# Power.net
KiCad netlist of a schematic drawn in Altium Designer
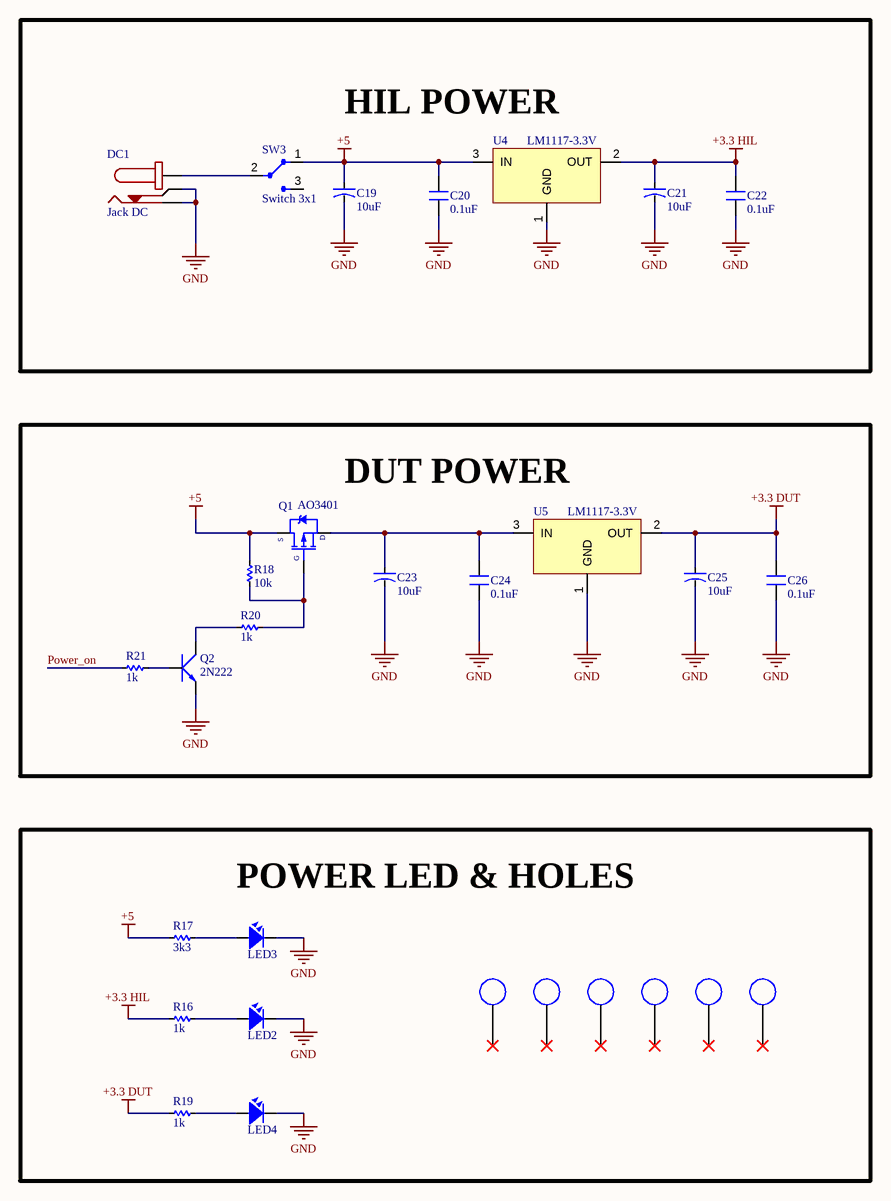
[diagram p0: Power.SchDoc]

(export (version "E")
  (design (tool "Eeschema 10.0.6"))
  (components
    (comp (ref "C19")
      (value "10uF")
      (footprint "CAP-ALU-SMD-4.5x5x1.4")
      (description "Capacitor (Semiconductor SIM Model)")
      (fields (field (name "PUBLISHER") "Altium Limited"))
      (libsource (lib "Library") (part "CN-ALU-DIP"))
    )
    (comp (ref "C20") (value "0.1uF") (footprint "CN-SMD-0603") (libsource (lib "Library") (part "CN")))
    (comp (ref "C21")
      (value "10uF")
      (footprint "CAP-ALU-SMD-4.5x5x1.4")
      (description "Capacitor (Semiconductor SIM Model)")
      (fields (field (name "PUBLISHER") "Altium Limited"))
      (libsource (lib "Library") (part "CN-ALU-DIP"))
    )
    (comp (ref "C22") (value "0.1uF") (footprint "CN-SMD-0603") (libsource (lib "Library") (part "CN")))
    (comp (ref "C23")
      (value "10uF")
      (footprint "CAP-ALU-SMD-4.5x5x1.4")
      (description "Capacitor (Semiconductor SIM Model)")
      (fields (field (name "PUBLISHER") "Altium Limited"))
      (libsource (lib "Library") (part "CN-ALU-DIP"))
    )
    (comp (ref "C24") (value "0.1uF") (footprint "CN-SMD-0603") (libsource (lib "Library") (part "CN")))
    (comp (ref "C25")
      (value "10uF")
      (footprint "CAP-ALU-SMD-4.5x5x1.4")
      (description "Capacitor (Semiconductor SIM Model)")
      (fields (field (name "PUBLISHER") "Altium Limited"))
      (libsource (lib "Library") (part "CN-ALU-DIP"))
    )
    (comp (ref "C26") (value "0.1uF") (footprint "CN-SMD-0603") (libsource (lib "Library") (part "CN")))
    (comp (ref "DC1")
      (value "Jack DC")
      (footprint "DC0")
      (description "Jack DC input")
      (libsource (lib "Library") (part "DCIN"))
    )
    (comp (ref "H1") (value "M3") (footprint "M3") (libsource (lib "Library") (part "M3")))
    (comp (ref "H2") (value "M3") (footprint "M3") (libsource (lib "Library") (part "M3")))
    (comp (ref "H3") (value "M3") (footprint "M3") (libsource (lib "Library") (part "M3")))
    (comp (ref "H4") (value "M3") (footprint "M3") (libsource (lib "Library") (part "M3")))
    (comp (ref "H5") (value "M3") (footprint "M3") (libsource (lib "Library") (part "M3")))
    (comp (ref "H6") (value "M3") (footprint "M3") (libsource (lib "Library") (part "M3")))
    (comp (ref "LED2") (value "LED") (footprint "LED-0805-Red") (libsource (lib "Library") (part "LED SMD")))
    (comp (ref "LED3") (value "LED") (footprint "LED-0805-Red") (libsource (lib "Library") (part "LED SMD")))
    (comp (ref "LED4") (value "LED") (footprint "LED-0805-Red") (libsource (lib "Library") (part "LED SMD")))
    (comp (ref "Q1")
      (value "AO3401")
      (footprint "SOT23-123")
      (description "P-MOS 30V 4A")
      (libsource (lib "Library") (part "AO3401"))
    )
    (comp (ref "Q2")
      (value "2N222")
      (footprint "SOT23-231")
      (description "NPN 600mW, ECB")
      (libsource (lib "Library") (part "2N222"))
    )
    (comp (ref "R16")
      (value "1k")
      (footprint "RES-SMD-0603")
      (description "Resistor")
      (fields
        (field (name "MANUFACTURER") "Generic Components")
        (field (name "PUBLISHER") "Altium Hobart Technology Centre")
      )
      (libsource (lib "Library") (part "Res-SMD"))
    )
    (comp (ref "R17")
      (value "3k3")
      (footprint "RES-SMD-0603")
      (description "Resistor")
      (fields
        (field (name "MANUFACTURER") "Generic Components")
        (field (name "PUBLISHER") "Altium Hobart Technology Centre")
      )
      (libsource (lib "Library") (part "Res-SMD"))
    )
    (comp (ref "R18")
      (value "10k")
      (footprint "RES-SMD-0603")
      (description "Resistor")
      (fields
        (field (name "MANUFACTURER") "Generic Components")
        (field (name "PUBLISHER") "Altium Hobart Technology Centre")
      )
      (libsource (lib "Library") (part "Res-SMD"))
    )
    (comp (ref "R19")
      (value "1k")
      (footprint "RES-SMD-0603")
      (description "Resistor")
      (fields
        (field (name "MANUFACTURER") "Generic Components")
        (field (name "PUBLISHER") "Altium Hobart Technology Centre")
      )
      (libsource (lib "Library") (part "Res-SMD"))
    )
    (comp (ref "R20")
      (value "1k")
      (footprint "RES-SMD-0603")
      (description "Resistor")
      (fields
        (field (name "MANUFACTURER") "Generic Components")
        (field (name "PUBLISHER") "Altium Hobart Technology Centre")
      )
      (libsource (lib "Library") (part "Res-SMD"))
    )
    (comp (ref "R21")
      (value "1k")
      (footprint "RES-SMD-0603")
      (description "Resistor")
      (fields
        (field (name "MANUFACTURER") "Generic Components")
        (field (name "PUBLISHER") "Altium Hobart Technology Centre")
      )
      (libsource (lib "Library") (part "Res-SMD"))
    )
    (comp (ref "SW3") (value "Switch 3x1") (footprint "SS12D00") (libsource (lib "Library") (part "SW3x1")))
    (comp (ref "U4")
      (value "LM1117-3.3V")
      (footprint "SOT223")
      (description "800mA Low-Dropout Linear Regulator")
      (fields (field (name "CREATOR") "Nguyen Ba Bien"))
      (libsource (lib "Library") (part "LM1117"))
    )
    (comp (ref "U5")
      (value "LM1117-3.3V")
      (footprint "SOT223")
      (description "800mA Low-Dropout Linear Regulator")
      (fields (field (name "CREATOR") "Nguyen Ba Bien"))
      (libsource (lib "Library") (part "LM1117"))
    )
  )
  (nets
    (net (code "1") (name "+3.3 DUT") (class "Default")
      (node (ref "C25") (pin "1") (pinfunction "1_1") (pintype "passive"))
      (node (ref "C26") (pin "2") (pinfunction "2_2") (pintype "passive"))
      (node (ref "R19") (pin "1") (pinfunction "1_1") (pintype "passive"))
      (node (ref "U5") (pin "2") (pinfunction "OUT_2") (pintype "passive"))
    )
    (net (code "2") (name "+3.3 HIL") (class "Default")
      (node (ref "C21") (pin "1") (pinfunction "1_1") (pintype "passive"))
      (node (ref "C22") (pin "2") (pinfunction "2_2") (pintype "passive"))
      (node (ref "R16") (pin "1") (pinfunction "1_1") (pintype "passive"))
      (node (ref "U4") (pin "2") (pinfunction "OUT_2") (pintype "passive"))
    )
    (net (code "3") (name "+5") (class "Default")
      (node (ref "C19") (pin "1") (pinfunction "1_1") (pintype "passive"))
      (node (ref "C20") (pin "2") (pinfunction "2_2") (pintype "passive"))
      (node (ref "Q1") (pin "3") (pinfunction "S_3") (pintype "passive"))
      (node (ref "R17") (pin "1") (pinfunction "1_1") (pintype "passive"))
      (node (ref "R18") (pin "2") (pinfunction "2_2") (pintype "passive"))
      (node (ref "SW3") (pin "1") (pintype "passive"))
      (node (ref "U4") (pin "3") (pinfunction "IN_3") (pintype "passive"))
    )
    (net (code "4") (name "/Power_on") (class "Default")
      (node (ref "R21") (pin "2") (pinfunction "2_2") (pintype "passive"))
    )
    (net (code "5") (name "GND") (class "Default")
      (node (ref "C19") (pin "2") (pinfunction "2_2") (pintype "passive"))
      (node (ref "C20") (pin "1") (pinfunction "1_1") (pintype "passive"))
      (node (ref "C21") (pin "2") (pinfunction "2_2") (pintype "passive"))
      (node (ref "C22") (pin "1") (pinfunction "1_1") (pintype "passive"))
      (node (ref "C23") (pin "2") (pinfunction "2_2") (pintype "passive"))
      (node (ref "C24") (pin "1") (pinfunction "1_1") (pintype "passive"))
      (node (ref "C25") (pin "2") (pinfunction "2_2") (pintype "passive"))
      (node (ref "C26") (pin "1") (pinfunction "1_1") (pintype "passive"))
      (node (ref "DC1") (pin "2") (pinfunction "TN_2") (pintype "passive"))
      (node (ref "DC1") (pin "3") (pinfunction "T_3") (pintype "passive"))
      (node (ref "LED2") (pin "2") (pinfunction "2_2") (pintype "passive"))
      (node (ref "LED3") (pin "2") (pinfunction "2_2") (pintype "passive"))
      (node (ref "LED4") (pin "2") (pinfunction "2_2") (pintype "passive"))
      (node (ref "Q2") (pin "1") (pinfunction "E_1") (pintype "passive"))
      (node (ref "U4") (pin "1") (pinfunction "GND_1") (pintype "passive"))
      (node (ref "U5") (pin "1") (pinfunction "GND_1") (pintype "passive"))
    )
    (net (code "6") (name "Net-(DC1-S)") (class "Default")
      (node (ref "DC1") (pin "1") (pinfunction "S_1") (pintype "power_in"))
      (node (ref "SW3") (pin "2") (pintype "passive"))
    )
    (net (code "7") (name "Net-(LED2-Pad1)") (class "Default")
      (node (ref "LED2") (pin "1") (pinfunction "1_1") (pintype "passive"))
      (node (ref "R16") (pin "2") (pinfunction "2_2") (pintype "passive"))
    )
    (net (code "8") (name "Net-(LED3-Pad1)") (class "Default")
      (node (ref "LED3") (pin "1") (pinfunction "1_1") (pintype "passive"))
      (node (ref "R17") (pin "2") (pinfunction "2_2") (pintype "passive"))
    )
    (net (code "9") (name "Net-(LED4-Pad1)") (class "Default")
      (node (ref "LED4") (pin "1") (pinfunction "1_1") (pintype "passive"))
      (node (ref "R19") (pin "2") (pinfunction "2_2") (pintype "passive"))
    )
    (net (code "10") (name "Net-(Q1-D)") (class "Default")
      (node (ref "C23") (pin "1") (pinfunction "1_1") (pintype "passive"))
      (node (ref "C24") (pin "2") (pinfunction "2_2") (pintype "passive"))
      (node (ref "Q1") (pin "2") (pinfunction "D_2") (pintype "passive"))
      (node (ref "U5") (pin "3") (pinfunction "IN_3") (pintype "passive"))
    )
    (net (code "11") (name "Net-(Q1-G)") (class "Default")
      (node (ref "Q1") (pin "1") (pinfunction "G_1") (pintype "passive"))
      (node (ref "R18") (pin "1") (pinfunction "1_1") (pintype "passive"))
      (node (ref "R20") (pin "1") (pinfunction "1_1") (pintype "passive"))
    )
    (net (code "12") (name "Net-(Q2-B)") (class "Default")
      (node (ref "Q2") (pin "2") (pinfunction "B_2") (pintype "passive"))
      (node (ref "R21") (pin "1") (pinfunction "1_1") (pintype "passive"))
    )
    (net (code "13") (name "Net-(Q2-C)") (class "Default")
      (node (ref "Q2") (pin "3") (pinfunction "C_3") (pintype "passive"))
      (node (ref "R20") (pin "2") (pinfunction "2_2") (pintype "passive"))
    )
    (net (code "14") (name "unconnected-(H1-76-Pad1)") (class "Default")
      (node (ref "H1") (pin "1") (pinfunction "76_1") (pintype "passive+no_connect"))
    )
    (net (code "15") (name "unconnected-(H2-76-Pad1)") (class "Default")
      (node (ref "H2") (pin "1") (pinfunction "76_1") (pintype "passive+no_connect"))
    )
    (net (code "16") (name "unconnected-(H3-76-Pad1)") (class "Default")
      (node (ref "H3") (pin "1") (pinfunction "76_1") (pintype "passive+no_connect"))
    )
    (net (code "17") (name "unconnected-(H4-76-Pad1)") (class "Default")
      (node (ref "H4") (pin "1") (pinfunction "76_1") (pintype "passive+no_connect"))
    )
    (net (code "18") (name "unconnected-(H5-76-Pad1)") (class "Default")
      (node (ref "H5") (pin "1") (pinfunction "76_1") (pintype "passive+no_connect"))
    )
    (net (code "19") (name "unconnected-(H6-76-Pad1)") (class "Default")
      (node (ref "H6") (pin "1") (pinfunction "76_1") (pintype "passive+no_connect"))
    )
    (net (code "20") (name "unconnected-(SW3-I{slash}O2-Pad3)") (class "Default")
      (node (ref "SW3") (pin "3") (pinfunction "I/O2_3") (pintype "passive"))
    )
  )
)
